# proiect.net
KiCad netlist of a schematic drawn in EAGLE
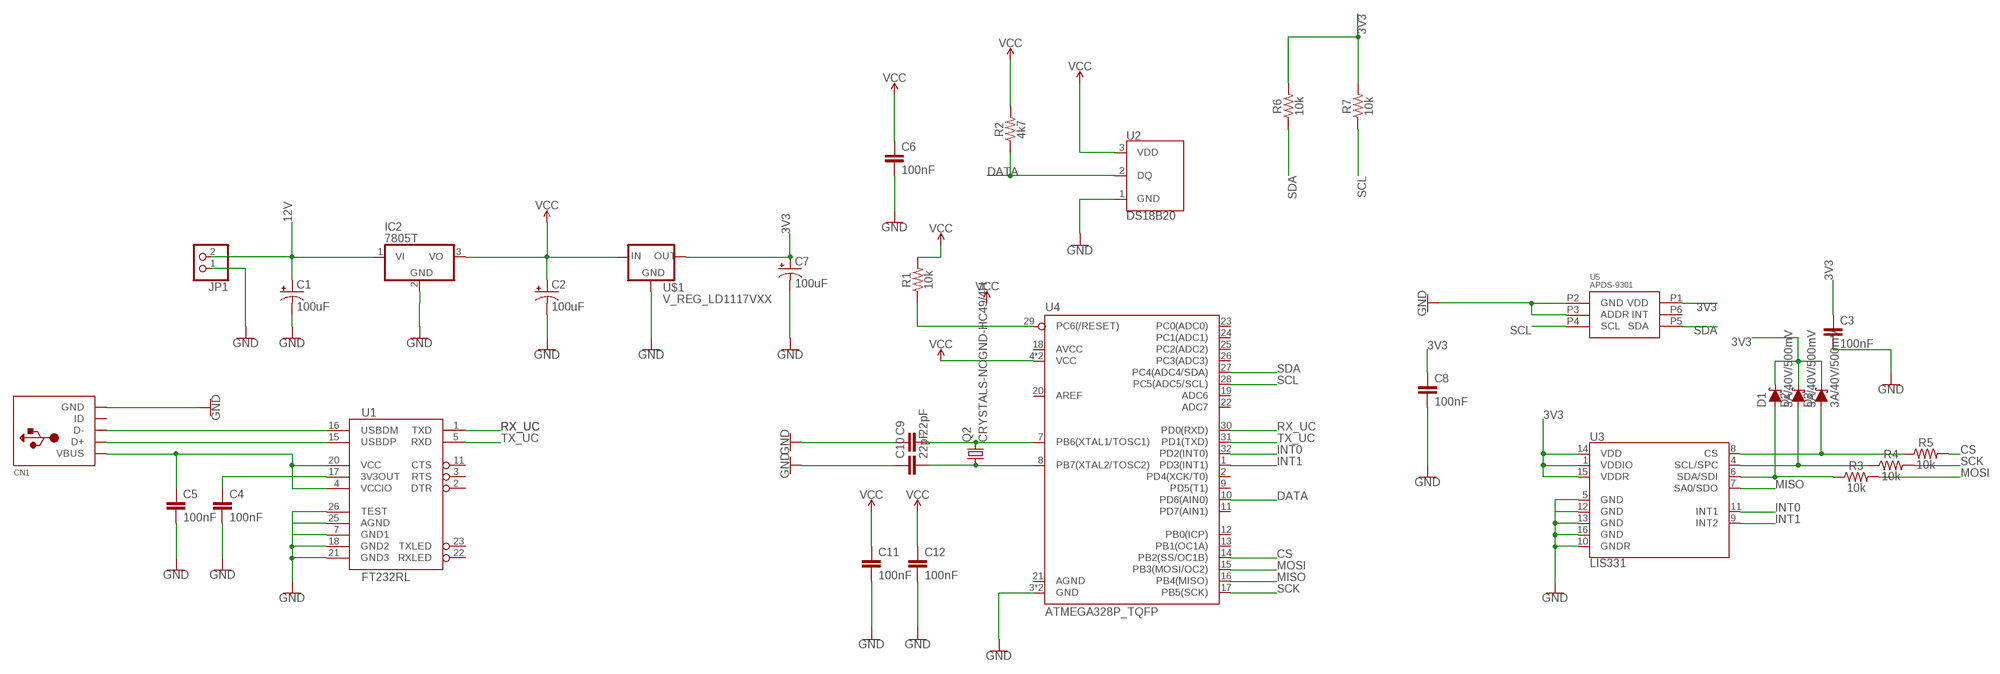
[diagram p0: schematic, sheet 1]

(export (version "E")
  (design (tool "Eeschema 10.0.6"))
  (components
    (comp (ref "C1")
      (value "100uF")
      (footprint "eagle-import:CPOL-RADIAL-2.5MM-6.5MM")
      (libsource (lib "eagle-import") (part "100UF-POLAR-RADIAL-2.5MM-25V-20%"))
    )
    (comp (ref "C2")
      (value "100uF")
      (footprint "eagle-import:CPOL-RADIAL-2.5MM-6.5MM")
      (libsource (lib "eagle-import") (part "100UF-POLAR-RADIAL-2.5MM-25V-20%"))
    )
    (comp (ref "C3")
      (value "100nF")
      (footprint "eagle-import:0603")
      (libsource (lib "eagle-import") (part "0.1UF-0603-25V-(+80/-20%)"))
    )
    (comp (ref "C4")
      (value "100nF")
      (footprint "eagle-import:0603")
      (libsource (lib "eagle-import") (part "0.1UF-0603-25V-(+80/-20%)"))
    )
    (comp (ref "C5")
      (value "100nF")
      (footprint "eagle-import:0603")
      (libsource (lib "eagle-import") (part "0.1UF-0603-25V-(+80/-20%)"))
    )
    (comp (ref "C6")
      (value "100nF")
      (footprint "eagle-import:0603")
      (libsource (lib "eagle-import") (part "0.1UF-0603-25V-(+80/-20%)"))
    )
    (comp (ref "C7")
      (value "100uF")
      (footprint "eagle-import:CPOL-RADIAL-2.5MM-6.5MM")
      (libsource (lib "eagle-import") (part "100UF-POLAR-RADIAL-2.5MM-25V-20%"))
    )
    (comp (ref "C8")
      (value "100nF")
      (footprint "eagle-import:0603")
      (libsource (lib "eagle-import") (part "0.1UF-0603-25V-(+80/-20%)"))
    )
    (comp (ref "C9")
      (value "22pF")
      (footprint "eagle-import:0603")
      (libsource (lib "eagle-import") (part "0.1UF-0603-25V-(+80/-20%)"))
    )
    (comp (ref "C10")
      (value "22pF")
      (footprint "eagle-import:0603")
      (libsource (lib "eagle-import") (part "0.1UF-0603-25V-(+80/-20%)"))
    )
    (comp (ref "C11")
      (value "100nF")
      (footprint "eagle-import:0603")
      (libsource (lib "eagle-import") (part "0.1UF-0603-25V-(+80/-20%)"))
    )
    (comp (ref "C12")
      (value "100nF")
      (footprint "eagle-import:0603")
      (libsource (lib "eagle-import") (part "0.1UF-0603-25V-(+80/-20%)"))
    )
    (comp (ref "CN1")
      (value "USBMINIB")
      (footprint "eagle-import:USB-MINIB")
      (libsource (lib "eagle-import") (part "USBMINIB"))
    )
    (comp (ref "D1")
      (value "3A/40V/500mV")
      (footprint "eagle-import:SMA-DIODE")
      (libsource (lib "eagle-import") (part "DIODE-SCHOTTKY-B340A"))
    )
    (comp (ref "D2")
      (value "3A/40V/500mV")
      (footprint "eagle-import:SMA-DIODE")
      (libsource (lib "eagle-import") (part "DIODE-SCHOTTKY-B340A"))
    )
    (comp (ref "D3")
      (value "3A/40V/500mV")
      (footprint "eagle-import:SMA-DIODE")
      (libsource (lib "eagle-import") (part "DIODE-SCHOTTKY-B340A"))
    )
    (comp (ref "IC2")
      (value "7805T")
      (footprint "eagle-import:TO220H")
      (libsource (lib "eagle-import") (part "78T05"))
    )
    (comp (ref "JP1")
      (value "PINHD-1X2")
      (footprint "eagle-import:1X02")
      (libsource (lib "eagle-import") (part "PINHD-1X2"))
    )
    (comp (ref "Q2")
      (value "CRYSTALS-NOGND-HC49/4H")
      (footprint "eagle-import:HC49")
      (libsource (lib "eagle-import") (part "CRYSTALS-NOGND-HC49/4H"))
    )
    (comp (ref "R1")
      (value "10k")
      (footprint "eagle-import:0603")
      (libsource (lib "eagle-import") (part "1KOHM-0603-1/10W-1%"))
    )
    (comp (ref "R2")
      (value "4k7")
      (footprint "eagle-import:0603")
      (libsource (lib "eagle-import") (part "1KOHM-0603-1/10W-1%"))
    )
    (comp (ref "R3")
      (value "10k")
      (footprint "eagle-import:0603")
      (libsource (lib "eagle-import") (part "1KOHM-0603-1/10W-1%"))
    )
    (comp (ref "R4")
      (value "10k")
      (footprint "eagle-import:0603")
      (libsource (lib "eagle-import") (part "1KOHM-0603-1/10W-1%"))
    )
    (comp (ref "R5")
      (value "10k")
      (footprint "eagle-import:0603")
      (libsource (lib "eagle-import") (part "1KOHM-0603-1/10W-1%"))
    )
    (comp (ref "R6")
      (value "10k")
      (footprint "eagle-import:0603")
      (libsource (lib "eagle-import") (part "1KOHM-0603-1/10W-1%"))
    )
    (comp (ref "R7")
      (value "10k")
      (footprint "eagle-import:0603")
      (libsource (lib "eagle-import") (part "1KOHM-0603-1/10W-1%"))
    )
    (comp (ref "U$1")
      (value "V_REG_LD1117VXX")
      (footprint "eagle-import:78XXL")
      (libsource (lib "eagle-import") (part "V_REG_LD1117VXX"))
    )
    (comp (ref "U1")
      (value "FT232RL")
      (footprint "eagle-import:SSOP28DB")
      (libsource (lib "eagle-import") (part "FT232RL-BASICSSOP"))
    )
    (comp (ref "U2")
      (value "DS18B20")
      (footprint "eagle-import:TO-92-AMMO")
      (libsource (lib "eagle-import") (part "DS18B20"))
    )
    (comp (ref "U3")
      (value "LIS331")
      (footprint "eagle-import:LGA-16-3X3")
      (libsource (lib "eagle-import") (part "LIS331"))
    )
    (comp (ref "U4")
      (value "ATMEGA328P_TQFP")
      (footprint "eagle-import:TQFP32-08")
      (libsource (lib "eagle-import") (part "ATMEGA328P_TQFP"))
    )
    (comp (ref "U5")
      (value "APDS-9301")
      (footprint "eagle-import:CHIPLED-6")
      (libsource (lib "eagle-import") (part "APDS-9301"))
    )
  )
  (nets
    (net (code "1") (name "/3V3") (class "Default")
      (node (ref "C3") (pin "1") (pinfunction "1_1") (pintype "passive"))
      (node (ref "C7") (pin "1") (pinfunction "+_1") (pintype "passive"))
      (node (ref "C8") (pin "1") (pinfunction "1_1") (pintype "passive"))
      (node (ref "D1") (pin "C") (pinfunction "C_C") (pintype "passive"))
      (node (ref "D2") (pin "C") (pinfunction "C_C") (pintype "passive"))
      (node (ref "D3") (pin "C") (pinfunction "C_C") (pintype "passive"))
      (node (ref "R6") (pin "2") (pinfunction "2_2") (pintype "passive"))
      (node (ref "R7") (pin "2") (pinfunction "2_2") (pintype "passive"))
      (node (ref "U$1") (pin "GND") (pinfunction "OUT_GND") (pintype "passive"))
      (node (ref "U3") (pin "1") (pinfunction "VDDIO_1") (pintype "bidirectional"))
      (node (ref "U3") (pin "14") (pinfunction "VDD_14") (pintype "bidirectional"))
      (node (ref "U3") (pin "15") (pinfunction "VDDR_15") (pintype "bidirectional"))
      (node (ref "U5") (pin "P1") (pinfunction "VDD_P1") (pintype "bidirectional"))
    )
    (net (code "2") (name "/12V") (class "Default")
      (node (ref "C1") (pin "1") (pinfunction "+_1") (pintype "passive"))
      (node (ref "IC2") (pin "1") (pinfunction "VI_1") (pintype "input"))
      (node (ref "JP1") (pin "2") (pinfunction "2_2") (pintype "passive"))
    )
    (net (code "3") (name "/CS") (class "Default")
      (node (ref "R5") (pin "2") (pinfunction "2_2") (pintype "passive"))
      (node (ref "U4") (pin "14") (pinfunction "PB2(SS/OC1B)_14") (pintype "bidirectional"))
    )
    (net (code "4") (name "/DATA") (class "Default")
      (node (ref "R2") (pin "1") (pinfunction "1_1") (pintype "passive"))
      (node (ref "U2") (pin "2") (pinfunction "DQ_2") (pintype "bidirectional"))
      (node (ref "U4") (pin "10") (pinfunction "PD6(AIN0)_10") (pintype "bidirectional"))
    )
    (net (code "5") (name "/INT0") (class "Default")
      (node (ref "U3") (pin "11") (pinfunction "INT1_11") (pintype "bidirectional"))
      (node (ref "U4") (pin "32") (pinfunction "PD2(INT0)_32") (pintype "bidirectional"))
    )
    (net (code "6") (name "/INT1") (class "Default")
      (node (ref "U3") (pin "9") (pinfunction "INT2_9") (pintype "bidirectional"))
      (node (ref "U4") (pin "1") (pinfunction "PD3(INT1)_1") (pintype "bidirectional"))
    )
    (net (code "7") (name "/MISO") (class "Default")
      (node (ref "U3") (pin "7") (pinfunction "SA0/SDO_7") (pintype "bidirectional"))
      (node (ref "U4") (pin "16") (pinfunction "PB4(MISO)_16") (pintype "bidirectional"))
    )
    (net (code "8") (name "/MOSI") (class "Default")
      (node (ref "R3") (pin "2") (pinfunction "2_2") (pintype "passive"))
      (node (ref "U4") (pin "15") (pinfunction "PB3(MOSI/OC2)_15") (pintype "bidirectional"))
    )
    (net (code "9") (name "/RX_UC") (class "Default")
      (node (ref "U1") (pin "1") (pinfunction "TXD_1") (pintype "output"))
      (node (ref "U4") (pin "30") (pinfunction "PD0(RXD)_30") (pintype "bidirectional"))
    )
    (net (code "10") (name "/SCK") (class "Default")
      (node (ref "R4") (pin "2") (pinfunction "2_2") (pintype "passive"))
      (node (ref "U4") (pin "17") (pinfunction "PB5(SCK)_17") (pintype "bidirectional"))
    )
    (net (code "11") (name "/SCL") (class "Default")
      (node (ref "R7") (pin "1") (pinfunction "1_1") (pintype "passive"))
      (node (ref "U4") (pin "28") (pinfunction "PC5(ADC5/SCL)_28") (pintype "bidirectional"))
      (node (ref "U5") (pin "P4") (pinfunction "SCL_P4") (pintype "bidirectional"))
    )
    (net (code "12") (name "/SDA") (class "Default")
      (node (ref "R6") (pin "1") (pinfunction "1_1") (pintype "passive"))
      (node (ref "U4") (pin "27") (pinfunction "PC4(ADC4/SDA)_27") (pintype "bidirectional"))
      (node (ref "U5") (pin "P5") (pinfunction "SDA_P5") (pintype "bidirectional"))
    )
    (net (code "13") (name "/TX_UC") (class "Default")
      (node (ref "U1") (pin "5") (pinfunction "RXD_5") (pintype "input"))
      (node (ref "U4") (pin "31") (pinfunction "PD1(TXD)_31") (pintype "bidirectional"))
    )
    (net (code "14") (name "GND") (class "Default")
      (node (ref "C1") (pin "2") (pinfunction "-_2") (pintype "passive"))
      (node (ref "C10") (pin "1") (pinfunction "1_1") (pintype "passive"))
      (node (ref "C11") (pin "2") (pinfunction "2_2") (pintype "passive"))
      (node (ref "C12") (pin "2") (pinfunction "2_2") (pintype "passive"))
      (node (ref "C2") (pin "2") (pinfunction "-_2") (pintype "passive"))
      (node (ref "C3") (pin "2") (pinfunction "2_2") (pintype "passive"))
      (node (ref "C4") (pin "2") (pinfunction "2_2") (pintype "passive"))
      (node (ref "C5") (pin "2") (pinfunction "2_2") (pintype "passive"))
      (node (ref "C6") (pin "2") (pinfunction "2_2") (pintype "passive"))
      (node (ref "C7") (pin "2") (pinfunction "-_2") (pintype "passive"))
      (node (ref "C8") (pin "2") (pinfunction "2_2") (pintype "passive"))
      (node (ref "C9") (pin "1") (pinfunction "1_1") (pintype "passive"))
      (node (ref "CN1") (pin "GND") (pinfunction "GND_GND") (pintype "power_in"))
      (node (ref "IC2") (pin "2") (pinfunction "GND_2") (pintype "passive"))
      (node (ref "JP1") (pin "1") (pinfunction "1_1") (pintype "passive"))
      (node (ref "U$1") (pin "IN") (pinfunction "GND_IN") (pintype "input"))
      (node (ref "U1") (pin "18") (pinfunction "GND2_18") (pintype "power_in"))
      (node (ref "U1") (pin "21") (pinfunction "GND3_21") (pintype "power_in"))
      (node (ref "U1") (pin "25") (pinfunction "AGND_25") (pintype "power_in"))
      (node (ref "U1") (pin "26") (pinfunction "TEST_26") (pintype "input"))
      (node (ref "U1") (pin "7") (pinfunction "GND1_7") (pintype "power_in"))
      (node (ref "U2") (pin "1") (pinfunction "GND_1") (pintype "power_in"))
      (node (ref "U3") (pin "10") (pinfunction "GNDR_10") (pintype "bidirectional"))
      (node (ref "U3") (pin "12") (pinfunction "GND_12") (pintype "bidirectional"))
      (node (ref "U3") (pin "13") (pinfunction "GND_13") (pintype "bidirectional"))
      (node (ref "U3") (pin "16") (pinfunction "GND_16") (pintype "bidirectional"))
      (node (ref "U3") (pin "5") (pinfunction "GND_5") (pintype "bidirectional"))
      (node (ref "U4") (pin "3") (pinfunction "GND_3") (pintype "bidirectional"))
      (node (ref "U4") (pin "5") (pinfunction "GND_5") (pintype "bidirectional"))
      (node (ref "U5") (pin "P2") (pinfunction "GND_P2") (pintype "bidirectional"))
      (node (ref "U5") (pin "P3") (pinfunction "ADDR_P3") (pintype "bidirectional"))
    )
    (net (code "15") (name "Net-(U1-3V3OUT)") (class "Default")
      (node (ref "C4") (pin "1") (pinfunction "1_1") (pintype "passive"))
      (node (ref "U1") (pin "17") (pinfunction "3V3OUT_17") (pintype "output"))
    )
    (net (code "16") (name "Net-(U1-USBDM)") (class "Default")
      (node (ref "CN1") (pin "D-") (pinfunction "D-_D-") (pintype "bidirectional"))
      (node (ref "U1") (pin "16") (pinfunction "USBDM_16") (pintype "bidirectional"))
    )
    (net (code "17") (name "Net-(U1-USBDP)") (class "Default")
      (node (ref "CN1") (pin "D+") (pinfunction "D+_D+") (pintype "bidirectional"))
      (node (ref "U1") (pin "15") (pinfunction "USBDP_15") (pintype "bidirectional"))
    )
    (net (code "18") (name "Net-(U1-VCC)") (class "Default")
      (node (ref "C5") (pin "1") (pinfunction "1_1") (pintype "passive"))
      (node (ref "CN1") (pin "VBUS") (pinfunction "VBUS_VBUS") (pintype "power_in"))
      (node (ref "U1") (pin "20") (pinfunction "VCC_20") (pintype "power_in"))
      (node (ref "U1") (pin "4") (pinfunction "VCCIO_4") (pintype "power_in"))
    )
    (net (code "19") (name "Net-(U3-CS)") (class "Default")
      (node (ref "D3") (pin "A") (pinfunction "A_A") (pintype "passive"))
      (node (ref "R5") (pin "1") (pinfunction "1_1") (pintype "passive"))
      (node (ref "U3") (pin "8") (pinfunction "CS_8") (pintype "bidirectional"))
    )
    (net (code "20") (name "Net-(U3-SCL{slash}SPC)") (class "Default")
      (node (ref "D2") (pin "A") (pinfunction "A_A") (pintype "passive"))
      (node (ref "R4") (pin "1") (pinfunction "1_1") (pintype "passive"))
      (node (ref "U3") (pin "4") (pinfunction "SCL/SPC_4") (pintype "bidirectional"))
    )
    (net (code "21") (name "Net-(U3-SDA{slash}SDI)") (class "Default")
      (node (ref "D1") (pin "A") (pinfunction "A_A") (pintype "passive"))
      (node (ref "R3") (pin "1") (pinfunction "1_1") (pintype "passive"))
      (node (ref "U3") (pin "6") (pinfunction "SDA/SDI_6") (pintype "bidirectional"))
    )
    (net (code "22") (name "Net-(U4-PB6(XTAL1{slash}TOSC1))") (class "Default")
      (node (ref "C9") (pin "2") (pinfunction "2_2") (pintype "passive"))
      (node (ref "Q2") (pin "2") (pinfunction "2_2") (pintype "passive"))
      (node (ref "U4") (pin "7") (pinfunction "PB6(XTAL1/TOSC1)_7") (pintype "bidirectional"))
    )
    (net (code "23") (name "Net-(U4-PB7(XTAL2{slash}TOSC2))") (class "Default")
      (node (ref "C10") (pin "2") (pinfunction "2_2") (pintype "passive"))
      (node (ref "Q2") (pin "1") (pinfunction "1_1") (pintype "passive"))
      (node (ref "U4") (pin "8") (pinfunction "PB7(XTAL2/TOSC2)_8") (pintype "bidirectional"))
    )
    (net (code "24") (name "Net-(U4-PC6({slash}RESET))") (class "Default")
      (node (ref "R1") (pin "1") (pinfunction "1_1") (pintype "passive"))
      (node (ref "U4") (pin "29") (pinfunction "PC6(/RESET)_29") (pintype "bidirectional"))
    )
    (net (code "25") (name "VCC") (class "Default")
      (node (ref "C11") (pin "1") (pinfunction "1_1") (pintype "passive"))
      (node (ref "C12") (pin "1") (pinfunction "1_1") (pintype "passive"))
      (node (ref "C2") (pin "1") (pinfunction "+_1") (pintype "passive"))
      (node (ref "C6") (pin "1") (pinfunction "1_1") (pintype "passive"))
      (node (ref "IC2") (pin "3") (pinfunction "VO_3") (pintype "passive"))
      (node (ref "R1") (pin "2") (pinfunction "2_2") (pintype "passive"))
      (node (ref "R2") (pin "2") (pinfunction "2_2") (pintype "passive"))
      (node (ref "U$1") (pin "OUT") (pinfunction "IN_OUT") (pintype "input"))
      (node (ref "U2") (pin "3") (pinfunction "VDD_3") (pintype "power_in"))
      (node (ref "U4") (pin "4") (pinfunction "VCC_4") (pintype "bidirectional"))
      (node (ref "U4") (pin "6") (pinfunction "VCC_6") (pintype "bidirectional"))
    )
    (net (code "26") (name "unconnected-(CN1-PadID)") (class "Default")
      (node (ref "CN1") (pin "ID") (pinfunction "ID_ID") (pintype "bidirectional"))
    )
    (net (code "27") (name "unconnected-(U1-CTS-Pad11)") (class "Default")
      (node (ref "U1") (pin "11") (pinfunction "CTS_11") (pintype "bidirectional"))
    )
    (net (code "28") (name "unconnected-(U1-DTR-Pad2)") (class "Default")
      (node (ref "U1") (pin "2") (pinfunction "DTR_2") (pintype "bidirectional"))
    )
    (net (code "29") (name "unconnected-(U1-RTS-Pad3)") (class "Default")
      (node (ref "U1") (pin "3") (pinfunction "RTS_3") (pintype "bidirectional"))
    )
    (net (code "30") (name "unconnected-(U1-RXLED-Pad22)") (class "Default")
      (node (ref "U1") (pin "22") (pinfunction "RXLED_22") (pintype "bidirectional"))
    )
    (net (code "31") (name "unconnected-(U1-TXLED-Pad23)") (class "Default")
      (node (ref "U1") (pin "23") (pinfunction "TXLED_23") (pintype "bidirectional"))
    )
    (net (code "32") (name "unconnected-(U4-ADC6-Pad19)") (class "Default")
      (node (ref "U4") (pin "19") (pinfunction "ADC6_19") (pintype "bidirectional"))
    )
    (net (code "33") (name "unconnected-(U4-ADC7-Pad22)") (class "Default")
      (node (ref "U4") (pin "22") (pinfunction "ADC7_22") (pintype "bidirectional"))
    )
    (net (code "34") (name "unconnected-(U4-AGND-Pad21)") (class "Default")
      (node (ref "U4") (pin "21") (pinfunction "AGND_21") (pintype "bidirectional"))
    )
    (net (code "35") (name "unconnected-(U4-AREF-Pad20)") (class "Default")
      (node (ref "U4") (pin "20") (pinfunction "AREF_20") (pintype "bidirectional"))
    )
    (net (code "36") (name "unconnected-(U4-AVCC-Pad18)") (class "Default")
      (node (ref "U4") (pin "18") (pinfunction "AVCC_18") (pintype "bidirectional"))
    )
    (net (code "37") (name "unconnected-(U4-PB0(ICP)-Pad12)") (class "Default")
      (node (ref "U4") (pin "12") (pinfunction "PB0(ICP)_12") (pintype "bidirectional"))
    )
    (net (code "38") (name "unconnected-(U4-PB1(OC1A)-Pad13)") (class "Default")
      (node (ref "U4") (pin "13") (pinfunction "PB1(OC1A)_13") (pintype "bidirectional"))
    )
    (net (code "39") (name "unconnected-(U4-PC0(ADC0)-Pad23)") (class "Default")
      (node (ref "U4") (pin "23") (pinfunction "PC0(ADC0)_23") (pintype "bidirectional"))
    )
    (net (code "40") (name "unconnected-(U4-PC1(ADC1)-Pad24)") (class "Default")
      (node (ref "U4") (pin "24") (pinfunction "PC1(ADC1)_24") (pintype "bidirectional"))
    )
    (net (code "41") (name "unconnected-(U4-PC2(ADC2)-Pad25)") (class "Default")
      (node (ref "U4") (pin "25") (pinfunction "PC2(ADC2)_25") (pintype "bidirectional"))
    )
    (net (code "42") (name "unconnected-(U4-PC3(ADC3)-Pad26)") (class "Default")
      (node (ref "U4") (pin "26") (pinfunction "PC3(ADC3)_26") (pintype "bidirectional"))
    )
    (net (code "43") (name "unconnected-(U4-PD4(XCK{slash}T0)-Pad2)") (class "Default")
      (node (ref "U4") (pin "2") (pinfunction "PD4(XCK/T0)_2") (pintype "bidirectional"))
    )
    (net (code "44") (name "unconnected-(U4-PD5(T1)-Pad9)") (class "Default")
      (node (ref "U4") (pin "9") (pinfunction "PD5(T1)_9") (pintype "bidirectional"))
    )
    (net (code "45") (name "unconnected-(U4-PD7(AIN1)-Pad11)") (class "Default")
      (node (ref "U4") (pin "11") (pinfunction "PD7(AIN1)_11") (pintype "bidirectional"))
    )
    (net (code "46") (name "unconnected-(U5-INT-PadP6)") (class "Default")
      (node (ref "U5") (pin "P6") (pinfunction "INT_P6") (pintype "bidirectional"))
    )
  )
)
